# FLIGHT-CONTROLLER_VERSION-2.net
KiCad netlist of a schematic drawn in EasyEDA Pro
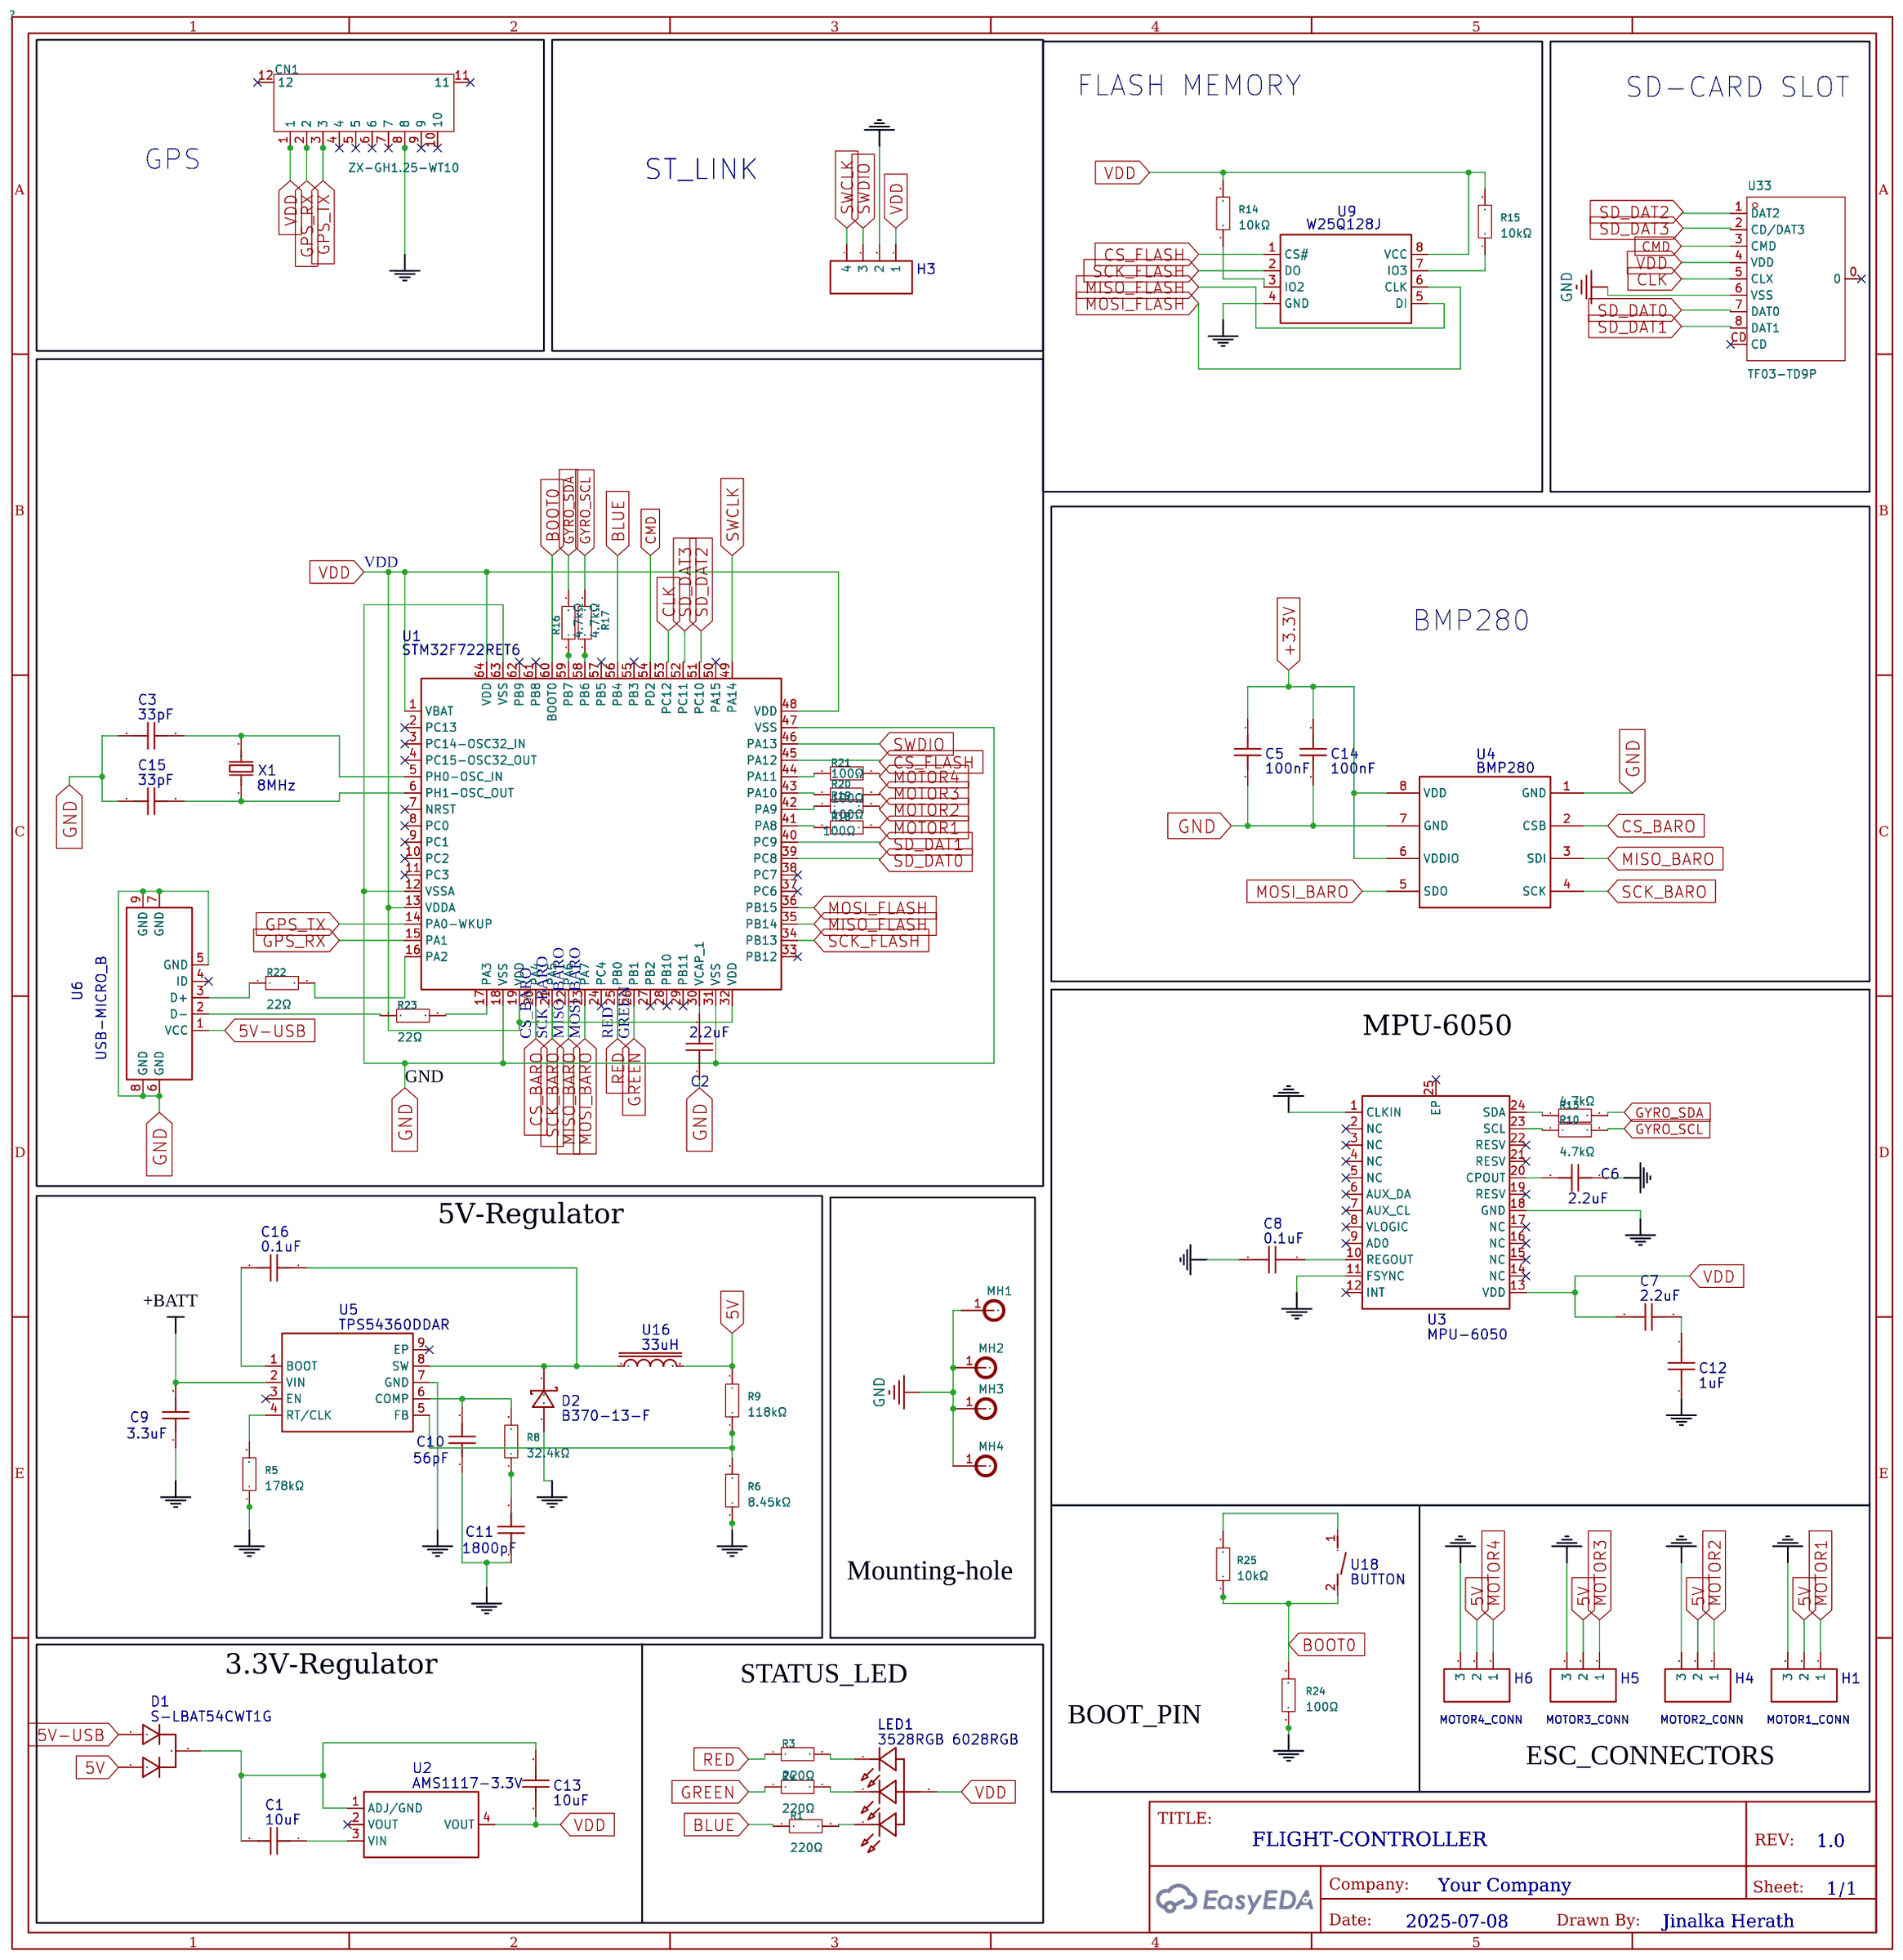
[diagram p0: schematic sheet]

(export (version "E")
  (design (tool "Eeschema 10.0.6"))
  (components
    (comp (ref "C1")
      (value "10uF")
      (footprint "easyedapro:C0603")
      (fields
        (field (name "Manufacturer Part") "C1608CH2A560J080AA")
        (field (name "Manufacturer") "TDK")
        (field (name "Contributor") "lcsc")
      )
      (libsource (lib "easyedapro") (part "10uF"))
    )
    (comp (ref "C2")
      (value "2.2uF")
      (footprint "easyedapro:CAP-SMD_L3.2-W2.5-1")
      (fields
        (field (name "Manufacturer Part") "25MU225MB23225")
        (field (name "Manufacturer") "rubycon(红宝石)")
        (field (name "Contributor") "lcsc")
      )
      (libsource (lib "easyedapro") (part "2.2uF"))
    )
    (comp (ref "C3")
      (value "33pF")
      (footprint "easyedapro:C0603")
      (fields
        (field (name "Manufacturer Part") "C1608CH2A560J080AA")
        (field (name "Manufacturer") "TDK")
        (field (name "Contributor") "lcsc")
      )
      (libsource (lib "easyedapro") (part "33pF"))
    )
    (comp (ref "C5")
      (value "100nF")
      (footprint "easyedapro:C0603")
      (fields
        (field (name "Manufacturer Part") "C1608CH2A560J080AA")
        (field (name "Manufacturer") "TDK")
        (field (name "Contributor") "lcsc")
      )
      (libsource (lib "easyedapro") (part "100nF"))
    )
    (comp (ref "C6")
      (value "2.2uF")
      (footprint "easyedapro:CAP-SMD_L3.2-W2.5-1")
      (fields
        (field (name "Manufacturer Part") "25MU225MB23225")
        (field (name "Manufacturer") "rubycon(红宝石)")
        (field (name "Contributor") "lcsc")
      )
      (libsource (lib "easyedapro") (part "2.2uF"))
    )
    (comp (ref "C7")
      (value "2.2uF")
      (footprint "easyedapro:CAP-SMD_L3.2-W2.5-1")
      (fields
        (field (name "Manufacturer Part") "25MU225MB23225")
        (field (name "Manufacturer") "rubycon(红宝石)")
        (field (name "Contributor") "lcsc")
      )
      (libsource (lib "easyedapro") (part "2.2uF"))
    )
    (comp (ref "C8")
      (value "0.1uF")
      (footprint "easyedapro:C0603")
      (fields
        (field (name "Manufacturer Part") "C1608CH2A560J080AA")
        (field (name "Manufacturer") "TDK")
        (field (name "Contributor") "lcsc")
      )
      (libsource (lib "easyedapro") (part "0.1uF"))
    )
    (comp (ref "C9")
      (value "3.3uF")
      (footprint "easyedapro:C0603")
      (fields
        (field (name "Manufacturer Part") "C1608CH2A560J080AA")
        (field (name "Manufacturer") "TDK")
        (field (name "Contributor") "lcsc")
      )
      (libsource (lib "easyedapro") (part "3.3uF"))
    )
    (comp (ref "C10")
      (value "56pF")
      (footprint "easyedapro:C0603")
      (fields
        (field (name "Manufacturer Part") "C1608CH2A560J080AA")
        (field (name "Manufacturer") "TDK")
        (field (name "Contributor") "lcsc")
      )
      (libsource (lib "easyedapro") (part "56pF"))
    )
    (comp (ref "C11")
      (value "1800pF")
      (footprint "easyedapro:C0603")
      (fields
        (field (name "Manufacturer Part") "C1608CH2A560J080AA")
        (field (name "Manufacturer") "TDK")
        (field (name "Contributor") "lcsc")
      )
      (libsource (lib "easyedapro") (part "1800pF"))
    )
    (comp (ref "C12")
      (value "1uF")
      (footprint "easyedapro:C0603")
      (fields
        (field (name "Manufacturer Part") "C1608CH2A560J080AA")
        (field (name "Manufacturer") "TDK")
        (field (name "Contributor") "lcsc")
      )
      (libsource (lib "easyedapro") (part "1uF"))
    )
    (comp (ref "C13")
      (value "10uF")
      (footprint "easyedapro:C0603")
      (fields
        (field (name "Manufacturer Part") "C1608CH2A560J080AA")
        (field (name "Manufacturer") "TDK")
        (field (name "Contributor") "lcsc")
      )
      (libsource (lib "easyedapro") (part "10uF"))
    )
    (comp (ref "C14")
      (value "100nF")
      (footprint "easyedapro:C0603")
      (fields
        (field (name "Manufacturer Part") "C1608CH2A560J080AA")
        (field (name "Manufacturer") "TDK")
        (field (name "Contributor") "lcsc")
      )
      (libsource (lib "easyedapro") (part "100nF"))
    )
    (comp (ref "C15")
      (value "33pF")
      (footprint "easyedapro:C0603")
      (fields
        (field (name "Manufacturer Part") "C1608CH2A560J080AA")
        (field (name "Manufacturer") "TDK")
        (field (name "Contributor") "lcsc")
      )
      (libsource (lib "easyedapro") (part "33pF"))
    )
    (comp (ref "C16")
      (value "0.1uF")
      (footprint "easyedapro:C0603")
      (fields
        (field (name "Manufacturer Part") "C1608CH2A560J080AA")
        (field (name "Manufacturer") "TDK")
        (field (name "Contributor") "lcsc")
      )
      (libsource (lib "easyedapro") (part "0.1uF"))
    )
    (comp (ref "CN1")
      (value "ZX-GH1.25-WT10")
      (footprint "easyedapro:CONN-SMD_ZX-GH1.25-WT10")
      (fields (field (name "Manufacturer") "Megastar(兆星)"))
      (libsource (lib "easyedapro") (part "ZX-GH1.25-WT10"))
    )
    (comp (ref "D1")
      (value "S-LBAT54CWT1G")
      (footprint "easyedapro:SC-70-3_L2.0-W1.3-P1.30-LS2.1-BR")
      (fields (field (name "Manufacturer") "LRC(乐山无线电)") (field (name "Contributor") "lcsc"))
      (libsource (lib "easyedapro") (part "S-LBAT54CWT1G"))
    )
    (comp (ref "D2")
      (value "B370-13-F")
      (footprint "easyedapro:SMC_L7.1-W6.2-LS8.1-RD")
      (fields (field (name "Manufacturer") "DIODES(美台)") (field (name "Contributor") "LCSC"))
      (libsource (lib "easyedapro") (part "B370-13-F"))
    )
    (comp (ref "H1")
      (value "MOTOR1_CONN")
      (footprint "easyedapro:HDR-F-2.54_1X3")
      (fields (field (name "Contributor") "LCEDA_Lib"))
      (libsource (lib "easyedapro") (part "MOTOR1_CONN"))
    )
    (comp (ref "H3")
      (value "ST_LINK")
      (footprint "easyedapro:HDR-F-2.54_1X4")
      (fields (field (name "Contributor") "LCEDA_Lib"))
      (libsource (lib "easyedapro") (part "ST_LINK"))
    )
    (comp (ref "H4")
      (value "MOTOR2_CONN")
      (footprint "easyedapro:HDR-F-2.54_1X3")
      (fields (field (name "Contributor") "LCEDA_Lib"))
      (libsource (lib "easyedapro") (part "MOTOR2_CONN"))
    )
    (comp (ref "H5")
      (value "MOTOR3_CONN")
      (footprint "easyedapro:HDR-F-2.54_1X3")
      (fields (field (name "Contributor") "LCEDA_Lib"))
      (libsource (lib "easyedapro") (part "MOTOR3_CONN"))
    )
    (comp (ref "H6")
      (value "MOTOR4_CONN")
      (footprint "easyedapro:HDR-F-2.54_1X3")
      (fields (field (name "Contributor") "LCEDA_Lib"))
      (libsource (lib "easyedapro") (part "MOTOR4_CONN"))
    )
    (comp (ref "LED1")
      (value "3528RGB 6028RGB")
      (footprint "easyedapro:LED-SMD_4P-L3.5-W2.8_3528RGB-6028RGB")
      (fields
        (field (name "Manufacturer Part") "3528反贴RGB 6028反贴RGB 缺口蓝色")
        (field (name "Contributor") "lcsc")
      )
      (libsource (lib "easyedapro") (part "3528RGB 6028RGB"))
    )
    (comp (ref "MH1")
      (value "~")
      (footprint "easyedapro:MH_7.5")
      (libsource (lib "easyedapro") (part "MH_7.5"))
    )
    (comp (ref "MH2")
      (value "~")
      (footprint "easyedapro:MH_7.5")
      (libsource (lib "easyedapro") (part "MH_7.5"))
    )
    (comp (ref "MH3")
      (value "~")
      (footprint "easyedapro:MH_7.5")
      (libsource (lib "easyedapro") (part "MH_7.5"))
    )
    (comp (ref "MH4")
      (value "~")
      (footprint "easyedapro:MH_7.5")
      (libsource (lib "easyedapro") (part "MH_7.5"))
    )
    (comp (ref "R1")
      (value "220Ω")
      (footprint "easyedapro:R0805")
      (fields
        (field (name "Manufacturer Part") "0805W8F2200T5E")
        (field (name "Manufacturer") "UNI-ROYAL(厚声)")
      )
      (libsource (lib "easyedapro") (part "0805W8F2200T5E"))
    )
    (comp (ref "R3")
      (value "220Ω")
      (footprint "easyedapro:R0805")
      (fields
        (field (name "Manufacturer Part") "0805W8F2200T5E")
        (field (name "Manufacturer") "UNI-ROYAL(厚声)")
      )
      (libsource (lib "easyedapro") (part "0805W8F2200T5E"))
    )
    (comp (ref "R4")
      (value "220Ω")
      (footprint "easyedapro:R0805")
      (fields
        (field (name "Manufacturer Part") "0805W8F2200T5E")
        (field (name "Manufacturer") "UNI-ROYAL(厚声)")
      )
      (libsource (lib "easyedapro") (part "0805W8F2200T5E"))
    )
    (comp (ref "R5")
      (value "178kΩ")
      (footprint "easyedapro:R0805")
      (fields
        (field (name "Manufacturer Part") "0805W8F2200T5E")
        (field (name "Manufacturer") "UNI-ROYAL(厚声)")
      )
      (libsource (lib "easyedapro") (part "0805W8F2200T5E"))
    )
    (comp (ref "R6")
      (value "8.45kΩ")
      (footprint "easyedapro:R0805")
      (fields
        (field (name "Manufacturer Part") "0805W8F2200T5E")
        (field (name "Manufacturer") "UNI-ROYAL(厚声)")
      )
      (libsource (lib "easyedapro") (part "0805W8F2200T5E"))
    )
    (comp (ref "R8")
      (value "32.4kΩ")
      (footprint "easyedapro:R0805")
      (fields
        (field (name "Manufacturer Part") "0805W8F2200T5E")
        (field (name "Manufacturer") "UNI-ROYAL(厚声)")
      )
      (libsource (lib "easyedapro") (part "0805W8F2200T5E"))
    )
    (comp (ref "R9")
      (value "118kΩ")
      (footprint "easyedapro:R0805")
      (fields
        (field (name "Manufacturer Part") "0805W8F2200T5E")
        (field (name "Manufacturer") "UNI-ROYAL(厚声)")
      )
      (libsource (lib "easyedapro") (part "0805W8F2200T5E"))
    )
    (comp (ref "R10")
      (value "4.7kΩ")
      (footprint "easyedapro:R0805")
      (fields
        (field (name "Manufacturer Part") "0805W8F2200T5E")
        (field (name "Manufacturer") "UNI-ROYAL(厚声)")
      )
      (libsource (lib "easyedapro") (part "0805W8F2200T5E"))
    )
    (comp (ref "R13")
      (value "4.7kΩ")
      (footprint "easyedapro:R0805")
      (fields
        (field (name "Manufacturer Part") "0805W8F2200T5E")
        (field (name "Manufacturer") "UNI-ROYAL(厚声)")
      )
      (libsource (lib "easyedapro") (part "0805W8F2200T5E"))
    )
    (comp (ref "R14")
      (value "10kΩ")
      (footprint "easyedapro:R0805")
      (fields
        (field (name "Manufacturer Part") "0805W8F2200T5E")
        (field (name "Manufacturer") "UNI-ROYAL(厚声)")
      )
      (libsource (lib "easyedapro") (part "0805W8F2200T5E"))
    )
    (comp (ref "R15")
      (value "10kΩ")
      (footprint "easyedapro:R0805")
      (fields
        (field (name "Manufacturer Part") "0805W8F2200T5E")
        (field (name "Manufacturer") "UNI-ROYAL(厚声)")
      )
      (libsource (lib "easyedapro") (part "0805W8F2200T5E"))
    )
    (comp (ref "R16")
      (value "4.7kΩ")
      (footprint "easyedapro:R0805")
      (fields
        (field (name "Manufacturer Part") "0805W8F2200T5E")
        (field (name "Manufacturer") "UNI-ROYAL(厚声)")
      )
      (libsource (lib "easyedapro") (part "0805W8F2200T5E"))
    )
    (comp (ref "R17")
      (value "4.7kΩ")
      (footprint "easyedapro:R0805")
      (fields
        (field (name "Manufacturer Part") "0805W8F2200T5E")
        (field (name "Manufacturer") "UNI-ROYAL(厚声)")
      )
      (libsource (lib "easyedapro") (part "0805W8F2200T5E"))
    )
    (comp (ref "R18")
      (value "100Ω")
      (footprint "easyedapro:R0805")
      (fields
        (field (name "Manufacturer Part") "0805W8F2200T5E")
        (field (name "Manufacturer") "UNI-ROYAL(厚声)")
      )
      (libsource (lib "easyedapro") (part "0805W8F2200T5E"))
    )
    (comp (ref "R19")
      (value "100Ω")
      (footprint "easyedapro:R0805")
      (fields
        (field (name "Manufacturer Part") "0805W8F2200T5E")
        (field (name "Manufacturer") "UNI-ROYAL(厚声)")
      )
      (libsource (lib "easyedapro") (part "0805W8F2200T5E"))
    )
    (comp (ref "R20")
      (value "100Ω")
      (footprint "easyedapro:R0805")
      (fields
        (field (name "Manufacturer Part") "0805W8F2200T5E")
        (field (name "Manufacturer") "UNI-ROYAL(厚声)")
      )
      (libsource (lib "easyedapro") (part "0805W8F2200T5E"))
    )
    (comp (ref "R21")
      (value "100Ω")
      (footprint "easyedapro:R0805")
      (fields
        (field (name "Manufacturer Part") "0805W8F2200T5E")
        (field (name "Manufacturer") "UNI-ROYAL(厚声)")
      )
      (libsource (lib "easyedapro") (part "0805W8F2200T5E"))
    )
    (comp (ref "R22")
      (value "22Ω")
      (footprint "easyedapro:R0805")
      (fields
        (field (name "Manufacturer Part") "0805W8F2200T5E")
        (field (name "Manufacturer") "UNI-ROYAL(厚声)")
      )
      (libsource (lib "easyedapro") (part "0805W8F2200T5E"))
    )
    (comp (ref "R23")
      (value "22Ω")
      (footprint "easyedapro:R0805")
      (fields
        (field (name "Manufacturer Part") "0805W8F2200T5E")
        (field (name "Manufacturer") "UNI-ROYAL(厚声)")
      )
      (libsource (lib "easyedapro") (part "0805W8F2200T5E"))
    )
    (comp (ref "R24")
      (value "100Ω")
      (footprint "easyedapro:R0805")
      (fields
        (field (name "Manufacturer Part") "0805W8F2200T5E")
        (field (name "Manufacturer") "UNI-ROYAL(厚声)")
      )
      (libsource (lib "easyedapro") (part "0805W8F2200T5E"))
    )
    (comp (ref "R25")
      (value "10kΩ")
      (footprint "easyedapro:R0805")
      (fields
        (field (name "Manufacturer Part") "0805W8F2200T5E")
        (field (name "Manufacturer") "UNI-ROYAL(厚声)")
      )
      (libsource (lib "easyedapro") (part "0805W8F2200T5E"))
    )
    (comp (ref "U1")
      (value "STM32F722RET6")
      (footprint "easyedapro:LQFP-64_L10.0-W10.0-P0.50-LS12.0-BL")
      (fields (field (name "Manufacturer") "ST(意法半导体)") (field (name "Contributor") "LCSC"))
      (libsource (lib "easyedapro") (part "STM32F722RET6"))
    )
    (comp (ref "U2")
      (value "AMS1117-3.3V")
      (footprint "easyedapro:SOT-223-4_L6.5-W3.5-P2.30-LS7.0-BR")
      (fields (field (name "Manufacturer") "WPMtek(维攀)") (field (name "Contributor") "LCSC"))
      (libsource (lib "easyedapro") (part "AMS1117-3.3V"))
    )
    (comp (ref "U3")
      (value "MPU-6050")
      (footprint "easyedapro:QFN-24_L4.0-W4.0-P0.50-BL-EP2.7")
      (fields (field (name "Manufacturer") "TDK InvenSense(应美盛)"))
      (libsource (lib "easyedapro") (part "MPU-6050_C24112"))
    )
    (comp (ref "U4")
      (value "BMP280")
      (footprint "easyedapro:LGA-8_L2.5-W2.0-P0.65_AMP6127")
      (fields (field (name "Manufacturer") "Bosch(博世)"))
      (libsource (lib "easyedapro") (part "BMP280"))
    )
    (comp (ref "U5")
      (value "TPS54360DDAR")
      (footprint "easyedapro:ESOP-8_L4.9-W3.9-P1.27-LS6.0-BL-EP")
      (fields
        (field (name "Manufacturer Part") "TPS54360DDAR(TOKMAS)")
        (field (name "Manufacturer") "Tokmas(托克马斯)")
        (field (name "Contributor") "lcsc")
      )
      (libsource (lib "easyedapro") (part "TPS54360DDAR(TOKMAS)"))
    )
    (comp (ref "U6")
      (value "USB-MICRO_B")
      (footprint "easyedapro:MICRO-USB-SMD_USB-MICRO_B")
      (fields (field (name "Contributor") "LCSC"))
      (libsource (lib "easyedapro") (part "USB-MICRO_B"))
    )
    (comp (ref "U9")
      (value "W25Q128J")
      (footprint "easyedapro:SOIC-8_L5.3-W5.3-P1.27-LS8.0-BL")
      (fields (field (name "Manufacturer Part") "W25Q128JVSIQ") (field (name "Manufacturer") "WINBOND(华邦)"))
      (libsource (lib "easyedapro") (part "W25Q128JVSIQTR"))
    )
    (comp (ref "U16")
      (value "33uH")
      (footprint "easyedapro:IND-SMD_L8.5-W8.0_SMS0850")
      (fields
        (field (name "Manufacturer Part") "SMS0850-330MT")
        (field (name "Manufacturer") "LanTu Micro(蓝图微电)")
        (field (name "Contributor") "lcsc")
      )
      (libsource (lib "easyedapro") (part "33uH"))
    )
    (comp (ref "U18")
      (value "BUTTON")
      (footprint "easyedapro:KEY-SMD_L6.0-W6.0-LS6.6")
      (fields (field (name "Contributor") "lcsc"))
      (libsource (lib "easyedapro") (part "BUTTON"))
    )
    (comp (ref "U33")
      (value "TF03-TD9P")
      (footprint "easyedapro:CONN-SMD_TF-001A-P")
      (fields (field (name "Manufacturer") "BXCONN(宝讯)"))
      (libsource (lib "easyedapro") (part "TF03-TD9P"))
    )
    (comp (ref "X1")
      (value "8MHz")
      (footprint "easyedapro:CRYSTAL-SMD_L3.2-W2.5_3225-8MHZ")
      (fields
        (field (name "Manufacturer Part") "X22EL89COI-111YLC-8M")
        (field (name "Manufacturer") "YXC(扬兴晶振)")
        (field (name "Contributor") "lcsc")
      )
      (libsource (lib "easyedapro") (part "8MHz"))
    )
  )
  (nets
    (net (code "1") (name "+3.3V") (class "Default")
      (node (ref "C14") (pin "1") (pinfunction "1_1") (pintype "unspecified"))
      (node (ref "C5") (pin "1") (pinfunction "1_1") (pintype "unspecified"))
      (node (ref "U4") (pin "6") (pinfunction "VDDIO_6") (pintype "unspecified"))
      (node (ref "U4") (pin "8") (pinfunction "VDD_8") (pintype "unspecified"))
    )
    (net (code "2") (name "+BATT") (class "Default")
      (node (ref "C9") (pin "2") (pinfunction "2_2") (pintype "unspecified"))
      (node (ref "U5") (pin "2") (pinfunction "VIN_2") (pintype "unspecified"))
    )
    (net (code "3") (name "5V") (class "Default")
      (node (ref "D1") (pin "2") (pinfunction "2_2") (pintype "unspecified"))
      (node (ref "H1") (pin "2") (pinfunction "2_2") (pintype "input"))
      (node (ref "H4") (pin "2") (pinfunction "2_2") (pintype "input"))
      (node (ref "H5") (pin "2") (pinfunction "2_2") (pintype "input"))
      (node (ref "H6") (pin "2") (pinfunction "2_2") (pintype "input"))
      (node (ref "R9") (pin "2") (pinfunction "2_2") (pintype "input"))
      (node (ref "U16") (pin "2") (pinfunction "2_2") (pintype "unspecified"))
    )
    (net (code "4") (name "5V-USB") (class "Default")
      (node (ref "D1") (pin "1") (pinfunction "1_1") (pintype "unspecified"))
      (node (ref "U6") (pin "1") (pinfunction "VCC_1") (pintype "unspecified"))
    )
    (net (code "5") (name "BLUE") (class "Default")
      (node (ref "R1") (pin "1") (pinfunction "1_1") (pintype "input"))
      (node (ref "U1") (pin "56") (pinfunction "PB4_56") (pintype "unspecified"))
    )
    (net (code "6") (name "BOOT0") (class "Default")
      (node (ref "R24") (pin "2") (pinfunction "2_2") (pintype "input"))
      (node (ref "R25") (pin "1") (pinfunction "1_1") (pintype "input"))
      (node (ref "U1") (pin "60") (pinfunction "BOOT0_60") (pintype "unspecified"))
      (node (ref "U18") (pin "2") (pinfunction "B_2") (pintype "unspecified"))
    )
    (net (code "7") (name "CLK") (class "Default")
      (node (ref "U1") (pin "53") (pinfunction "PC12_53") (pintype "unspecified"))
      (node (ref "U33") (pin "5") (pinfunction "CLX_5") (pintype "unspecified"))
    )
    (net (code "8") (name "CMD") (class "Default")
      (node (ref "U1") (pin "54") (pinfunction "PD2_54") (pintype "unspecified"))
      (node (ref "U33") (pin "3") (pinfunction "CMD_3") (pintype "unspecified"))
    )
    (net (code "9") (name "CS_BARO") (class "Default")
      (node (ref "U1") (pin "20") (pinfunction "PA4_20") (pintype "unspecified"))
      (node (ref "U4") (pin "2") (pinfunction "CSB_2") (pintype "unspecified"))
    )
    (net (code "10") (name "CS_FLASH") (class "Default")
      (node (ref "U1") (pin "45") (pinfunction "PA12_45") (pintype "unspecified"))
      (node (ref "U9") (pin "1") (pinfunction "CS#_1") (pintype "unspecified"))
    )
    (net (code "11") (name "GND") (class "Default")
      (node (ref "C10") (pin "1") (pinfunction "1_1") (pintype "unspecified"))
      (node (ref "C11") (pin "1") (pinfunction "1_1") (pintype "unspecified"))
      (node (ref "C12") (pin "2") (pinfunction "2_2") (pintype "unspecified"))
      (node (ref "C14") (pin "2") (pinfunction "2_2") (pintype "unspecified"))
      (node (ref "C15") (pin "1") (pinfunction "1_1") (pintype "unspecified"))
      (node (ref "C2") (pin "1") (pinfunction "1_1") (pintype "unspecified"))
      (node (ref "C3") (pin "1") (pinfunction "1_1") (pintype "unspecified"))
      (node (ref "C5") (pin "2") (pinfunction "2_2") (pintype "unspecified"))
      (node (ref "C6") (pin "1") (pinfunction "1_1") (pintype "unspecified"))
      (node (ref "C8") (pin "2") (pinfunction "2_2") (pintype "unspecified"))
      (node (ref "C9") (pin "1") (pinfunction "1_1") (pintype "unspecified"))
      (node (ref "CN1") (pin "8") (pinfunction "8_8") (pintype "unspecified"))
      (node (ref "D2") (pin "2") (pinfunction "A_2") (pintype "unspecified"))
      (node (ref "H1") (pin "3") (pinfunction "3_3") (pintype "input"))
      (node (ref "H3") (pin "2") (pinfunction "2_2") (pintype "unspecified"))
      (node (ref "H4") (pin "3") (pinfunction "3_3") (pintype "input"))
      (node (ref "H5") (pin "3") (pinfunction "3_3") (pintype "input"))
      (node (ref "H6") (pin "3") (pinfunction "3_3") (pintype "input"))
      (node (ref "MH1") (pin "1") (pinfunction "1_1") (pintype "input"))
      (node (ref "MH2") (pin "1") (pinfunction "1_1") (pintype "input"))
      (node (ref "MH3") (pin "1") (pinfunction "1_1") (pintype "input"))
      (node (ref "MH4") (pin "1") (pinfunction "1_1") (pintype "input"))
      (node (ref "R24") (pin "1") (pinfunction "1_1") (pintype "input"))
      (node (ref "R5") (pin "1") (pinfunction "1_1") (pintype "input"))
      (node (ref "R6") (pin "1") (pinfunction "1_1") (pintype "input"))
      (node (ref "U1") (pin "12") (pinfunction "VSSA_12") (pintype "unspecified"))
      (node (ref "U1") (pin "18") (pinfunction "VSS_18") (pintype "unspecified"))
      (node (ref "U1") (pin "31") (pinfunction "VSS_31") (pintype "unspecified"))
      (node (ref "U1") (pin "47") (pinfunction "VSS_47") (pintype "unspecified"))
      (node (ref "U1") (pin "63") (pinfunction "VSS_63") (pintype "unspecified"))
      (node (ref "U3") (pin "1") (pinfunction "CLKIN_1") (pintype "unspecified"))
      (node (ref "U3") (pin "11") (pinfunction "FSYNC_11") (pintype "unspecified"))
      (node (ref "U3") (pin "18") (pinfunction "GND_18") (pintype "unspecified"))
      (node (ref "U33") (pin "6") (pinfunction "VSS_6") (pintype "unspecified"))
      (node (ref "U4") (pin "1") (pinfunction "GND_1") (pintype "unspecified"))
      (node (ref "U4") (pin "7") (pinfunction "GND_7") (pintype "unspecified"))
      (node (ref "U5") (pin "7") (pinfunction "GND_7") (pintype "unspecified"))
      (node (ref "U6") (pin "5") (pinfunction "GND_5") (pintype "unspecified"))
      (node (ref "U6") (pin "6") (pinfunction "GND_6") (pintype "unspecified"))
      (node (ref "U6") (pin "7") (pinfunction "GND_7") (pintype "unspecified"))
      (node (ref "U6") (pin "8") (pinfunction "GND_8") (pintype "unspecified"))
      (node (ref "U6") (pin "9") (pinfunction "GND_9") (pintype "unspecified"))
      (node (ref "U9") (pin "4") (pinfunction "GND_4") (pintype "unspecified"))
    )
    (net (code "12") (name "GPS_RX") (class "Default")
      (node (ref "CN1") (pin "2") (pinfunction "2_2") (pintype "unspecified"))
      (node (ref "U1") (pin "15") (pinfunction "PA1_15") (pintype "unspecified"))
    )
    (net (code "13") (name "GPS_TX") (class "Default")
      (node (ref "CN1") (pin "3") (pinfunction "3_3") (pintype "unspecified"))
      (node (ref "U1") (pin "14") (pinfunction "PA0-WKUP_14") (pintype "unspecified"))
    )
    (net (code "14") (name "GREEN") (class "Default")
      (node (ref "R4") (pin "1") (pinfunction "1_1") (pintype "input"))
      (node (ref "U1") (pin "26") (pinfunction "PB1_26") (pintype "unspecified"))
    )
    (net (code "15") (name "GYRO_SCL") (class "Default")
      (node (ref "R10") (pin "2") (pinfunction "2_2") (pintype "input"))
      (node (ref "R17") (pin "2") (pinfunction "2_2") (pintype "input"))
    )
    (net (code "16") (name "GYRO_SDA") (class "Default")
      (node (ref "R13") (pin "2") (pinfunction "2_2") (pintype "input"))
      (node (ref "R16") (pin "2") (pinfunction "2_2") (pintype "input"))
    )
    (net (code "17") (name "MISO_BARO") (class "Default")
      (node (ref "U1") (pin "22") (pinfunction "PA6_22") (pintype "unspecified"))
      (node (ref "U4") (pin "3") (pinfunction "SDI_3") (pintype "unspecified"))
    )
    (net (code "18") (name "MISO_FLASH") (class "Default")
      (node (ref "U1") (pin "35") (pinfunction "PB14_35") (pintype "unspecified"))
      (node (ref "U9") (pin "5") (pinfunction "DI_5") (pintype "unspecified"))
    )
    (net (code "19") (name "MOSI_BARO") (class "Default")
      (node (ref "U1") (pin "23") (pinfunction "PA7_23") (pintype "unspecified"))
      (node (ref "U4") (pin "5") (pinfunction "SDO_5") (pintype "unspecified"))
    )
    (net (code "20") (name "MOSI_FLASH") (class "Default")
      (node (ref "U1") (pin "36") (pinfunction "PB15_36") (pintype "unspecified"))
      (node (ref "U9") (pin "6") (pinfunction "CLK_6") (pintype "unspecified"))
    )
    (net (code "21") (name "MOTOR1") (class "Default")
      (node (ref "H1") (pin "1") (pinfunction "1_1") (pintype "input"))
      (node (ref "R18") (pin "2") (pinfunction "2_2") (pintype "input"))
    )
    (net (code "22") (name "MOTOR2") (class "Default")
      (node (ref "H4") (pin "1") (pinfunction "1_1") (pintype "input"))
      (node (ref "R19") (pin "2") (pinfunction "2_2") (pintype "input"))
    )
    (net (code "23") (name "MOTOR3") (class "Default")
      (node (ref "H5") (pin "1") (pinfunction "1_1") (pintype "input"))
      (node (ref "R20") (pin "2") (pinfunction "2_2") (pintype "input"))
    )
    (net (code "24") (name "MOTOR4") (class "Default")
      (node (ref "H6") (pin "1") (pinfunction "1_1") (pintype "input"))
      (node (ref "R21") (pin "2") (pinfunction "2_2") (pintype "input"))
    )
    (net (code "25") (name "Net-(C11-Pad2)") (class "Default")
      (node (ref "C11") (pin "2") (pinfunction "2_2") (pintype "unspecified"))
      (node (ref "R8") (pin "1") (pinfunction "1_1") (pintype "input"))
    )
    (net (code "26") (name "Net-(C12-Pad1)") (class "Default")
      (node (ref "C12") (pin "1") (pinfunction "1_1") (pintype "unspecified"))
      (node (ref "C7") (pin "1") (pinfunction "1_1") (pintype "unspecified"))
    )
    (net (code "27") (name "Net-(D2-C)") (class "Default")
      (node (ref "C16") (pin "1") (pinfunction "1_1") (pintype "unspecified"))
      (node (ref "D2") (pin "1") (pinfunction "C_1") (pintype "unspecified"))
      (node (ref "U16") (pin "1") (pinfunction "1_1") (pintype "unspecified"))
      (node (ref "U5") (pin "8") (pinfunction "SW_8") (pintype "unspecified"))
    )
    (net (code "28") (name "Net-(LED1-B)") (class "Default")
      (node (ref "LED1") (pin "1") (pinfunction "B_1") (pintype "unspecified"))
      (node (ref "R4") (pin "2") (pinfunction "2_2") (pintype "input"))
    )
    (net (code "29") (name "Net-(LED1-G)") (class "Default")
      (node (ref "LED1") (pin "4") (pinfunction "G_4") (pintype "unspecified"))
      (node (ref "R1") (pin "2") (pinfunction "2_2") (pintype "input"))
    )
    (net (code "30") (name "Net-(LED1-R)") (class "Default")
      (node (ref "LED1") (pin "2") (pinfunction "R_2") (pintype "unspecified"))
      (node (ref "R3") (pin "2") (pinfunction "2_2") (pintype "input"))
    )
    (net (code "31") (name "Net-(U1-PA2)") (class "Default")
      (node (ref "R22") (pin "2") (pinfunction "2_2") (pintype "input"))
      (node (ref "U1") (pin "16") (pinfunction "PA2_16") (pintype "unspecified"))
    )
    (net (code "32") (name "Net-(U1-PA3)") (class "Default")
      (node (ref "R23") (pin "2") (pinfunction "2_2") (pintype "input"))
      (node (ref "U1") (pin "17") (pinfunction "PA3_17") (pintype "unspecified"))
    )
    (net (code "33") (name "Net-(U1-PA8)") (class "Default")
      (node (ref "R18") (pin "1") (pinfunction "1_1") (pintype "input"))
      (node (ref "U1") (pin "41") (pinfunction "PA8_41") (pintype "unspecified"))
    )
    (net (code "34") (name "Net-(U1-PA9)") (class "Default")
      (node (ref "R19") (pin "1") (pinfunction "1_1") (pintype "input"))
      (node (ref "U1") (pin "42") (pinfunction "PA9_42") (pintype "unspecified"))
    )
    (net (code "35") (name "Net-(U1-PA10)") (class "Default")
      (node (ref "R20") (pin "1") (pinfunction "1_1") (pintype "input"))
      (node (ref "U1") (pin "43") (pinfunction "PA10_43") (pintype "unspecified"))
    )
    (net (code "36") (name "Net-(U1-PA11)") (class "Default")
      (node (ref "R21") (pin "1") (pinfunction "1_1") (pintype "input"))
      (node (ref "U1") (pin "44") (pinfunction "PA11_44") (pintype "unspecified"))
    )
    (net (code "37") (name "Net-(U1-PB6)") (class "Default")
      (node (ref "R17") (pin "1") (pinfunction "1_1") (pintype "input"))
      (node (ref "U1") (pin "58") (pinfunction "PB6_58") (pintype "unspecified"))
    )
    (net (code "38") (name "Net-(U1-PB7)") (class "Default")
      (node (ref "R16") (pin "1") (pinfunction "1_1") (pintype "input"))
      (node (ref "U1") (pin "59") (pinfunction "PB7_59") (pintype "unspecified"))
    )
    (net (code "39") (name "Net-(U1-PH0-OSC_IN)") (class "Default")
      (node (ref "C3") (pin "2") (pinfunction "2_2") (pintype "unspecified"))
      (node (ref "U1") (pin "5") (pinfunction "PH0-OSC_IN_5") (pintype "unspecified"))
      (node (ref "X1") (pin "2") (pinfunction "2_2") (pintype "unspecified"))
    )
    (net (code "40") (name "Net-(U1-PH1-OSC_OUT)") (class "Default")
      (node (ref "C15") (pin "2") (pinfunction "2_2") (pintype "unspecified"))
      (node (ref "U1") (pin "6") (pinfunction "PH1-OSC_OUT_6") (pintype "unspecified"))
      (node (ref "X1") (pin "1") (pinfunction "1_1") (pintype "unspecified"))
    )
    (net (code "41") (name "Net-(U1-VCAP_1)") (class "Default")
      (node (ref "C2") (pin "2") (pinfunction "2_2") (pintype "unspecified"))
      (node (ref "U1") (pin "30") (pinfunction "VCAP_1_30") (pintype "unspecified"))
    )
    (net (code "42") (name "Net-(U2-ADJ{slash}GND)") (class "Default")
      (node (ref "C1") (pin "2") (pinfunction "2_2") (pintype "unspecified"))
      (node (ref "C13") (pin "1") (pinfunction "1_1") (pintype "unspecified"))
      (node (ref "D1") (pin "3") (pinfunction "3_3") (pintype "unspecified"))
      (node (ref "U2") (pin "1") (pinfunction "ADJ/GND_1") (pintype "unspecified"))
    )
    (net (code "43") (name "Net-(U2-VIN)") (class "Default")
      (node (ref "C1") (pin "1") (pinfunction "1_1") (pintype "unspecified"))
      (node (ref "U2") (pin "3") (pinfunction "VIN_3") (pintype "unspecified"))
    )
    (net (code "44") (name "Net-(U3-CPOUT)") (class "Default")
      (node (ref "C6") (pin "2") (pinfunction "2_2") (pintype "unspecified"))
      (node (ref "U3") (pin "20") (pinfunction "CPOUT_20") (pintype "unspecified"))
    )
    (net (code "45") (name "Net-(U3-REGOUT)") (class "Default")
      (node (ref "C8") (pin "1") (pinfunction "1_1") (pintype "unspecified"))
      (node (ref "U3") (pin "10") (pinfunction "REGOUT_10") (pintype "unspecified"))
    )
    (net (code "46") (name "Net-(U3-SCL)") (class "Default")
      (node (ref "R10") (pin "1") (pinfunction "1_1") (pintype "input"))
      (node (ref "U3") (pin "23") (pinfunction "SCL_23") (pintype "unspecified"))
    )
    (net (code "47") (name "Net-(U3-SDA)") (class "Default")
      (node (ref "R13") (pin "1") (pinfunction "1_1") (pintype "input"))
      (node (ref "U3") (pin "24") (pinfunction "SDA_24") (pintype "unspecified"))
    )
    (net (code "48") (name "Net-(U5-BOOT)") (class "Default")
      (node (ref "C16") (pin "2") (pinfunction "2_2") (pintype "unspecified"))
      (node (ref "U5") (pin "1") (pinfunction "BOOT_1") (pintype "unspecified"))
    )
    (net (code "49") (name "Net-(U5-COMP)") (class "Default")
      (node (ref "C10") (pin "2") (pinfunction "2_2") (pintype "unspecified"))
      (node (ref "R8") (pin "2") (pinfunction "2_2") (pintype "input"))
      (node (ref "U5") (pin "6") (pinfunction "COMP_6") (pintype "unspecified"))
    )
    (net (code "50") (name "Net-(U5-FB)") (class "Default")
      (node (ref "R6") (pin "2") (pinfunction "2_2") (pintype "input"))
      (node (ref "R9") (pin "1") (pinfunction "1_1") (pintype "input"))
      (node (ref "U5") (pin "5") (pinfunction "FB_5") (pintype "unspecified"))
    )
    (net (code "51") (name "Net-(U5-RT{slash}CLK)") (class "Default")
      (node (ref "R5") (pin "2") (pinfunction "2_2") (pintype "input"))
      (node (ref "U5") (pin "4") (pinfunction "RT/CLK_4") (pintype "unspecified"))
    )
    (net (code "52") (name "Net-(U6-D+)") (class "Default")
      (node (ref "R22") (pin "1") (pinfunction "1_1") (pintype "input"))
      (node (ref "U6") (pin "3") (pinfunction "D+_3") (pintype "unspecified"))
    )
    (net (code "53") (name "Net-(U6-D-)") (class "Default")
      (node (ref "R23") (pin "1") (pinfunction "1_1") (pintype "input"))
      (node (ref "U6") (pin "2") (pinfunction "D-_2") (pintype "unspecified"))
    )
    (net (code "54") (name "Net-(U9-IO2)") (class "Default")
      (node (ref "R14") (pin "1") (pinfunction "1_1") (pintype "input"))
      (node (ref "U9") (pin "3") (pinfunction "IO2_3") (pintype "unspecified"))
    )
    (net (code "55") (name "Net-(U9-IO3)") (class "Default")
      (node (ref "R15") (pin "1") (pinfunction "1_1") (pintype "input"))
      (node (ref "U9") (pin "7") (pinfunction "IO3_7") (pintype "unspecified"))
    )
    (net (code "56") (name "Net-(U18-A)") (class "Default")
      (node (ref "R25") (pin "2") (pinfunction "2_2") (pintype "input"))
      (node (ref "U18") (pin "1") (pinfunction "A_1") (pintype "unspecified"))
    )
    (net (code "57") (name "RED") (class "Default")
      (node (ref "R3") (pin "1") (pinfunction "1_1") (pintype "input"))
      (node (ref "U1") (pin "25") (pinfunction "PB0_25") (pintype "unspecified"))
    )
    (net (code "58") (name "SCK_BARO") (class "Default")
      (node (ref "U1") (pin "21") (pinfunction "PA5_21") (pintype "unspecified"))
      (node (ref "U4") (pin "4") (pinfunction "SCK_4") (pintype "unspecified"))
    )
    (net (code "59") (name "SCK_FLASH") (class "Default")
      (node (ref "U1") (pin "34") (pinfunction "PB13_34") (pintype "unspecified"))
      (node (ref "U9") (pin "2") (pinfunction "DO_2") (pintype "unspecified"))
    )
    (net (code "60") (name "SD_DAT0") (class "Default")
      (node (ref "U1") (pin "39") (pinfunction "PC8_39") (pintype "unspecified"))
      (node (ref "U33") (pin "7") (pinfunction "DAT0_7") (pintype "unspecified"))
    )
    (net (code "61") (name "SD_DAT1") (class "Default")
      (node (ref "U1") (pin "40") (pinfunction "PC9_40") (pintype "unspecified"))
      (node (ref "U33") (pin "8") (pinfunction "DAT1_8") (pintype "unspecified"))
    )
    (net (code "62") (name "SD_DAT2") (class "Default")
      (node (ref "U1") (pin "51") (pinfunction "PC10_51") (pintype "unspecified"))
      (node (ref "U33") (pin "1") (pinfunction "DAT2_1") (pintype "unspecified"))
    )
    (net (code "63") (name "SD_DAT3") (class "Default")
      (node (ref "U1") (pin "52") (pinfunction "PC11_52") (pintype "unspecified"))
      (node (ref "U33") (pin "2") (pinfunction "CD/DAT3_2") (pintype "unspecified"))
    )
    (net (code "64") (name "SWCLK") (class "Default")
      (node (ref "H3") (pin "4") (pinfunction "4_4") (pintype "unspecified"))
      (node (ref "U1") (pin "49") (pinfunction "PA14_49") (pintype "unspecified"))
    )
    (net (code "65") (name "SWDIO") (class "Default")
      (node (ref "H3") (pin "3") (pinfunction "3_3") (pintype "unspecified"))
      (node (ref "U1") (pin "46") (pinfunction "PA13_46") (pintype "unspecified"))
    )
    (net (code "66") (name "VDD") (class "Default")
      (node (ref "C13") (pin "2") (pinfunction "2_2") (pintype "unspecified"))
      (node (ref "C7") (pin "2") (pinfunction "2_2") (pintype "unspecified"))
      (node (ref "CN1") (pin "1") (pinfunction "1_1") (pintype "unspecified"))
      (node (ref "H3") (pin "1") (pinfunction "1_1") (pintype "unspecified"))
      (node (ref "LED1") (pin "3") (pinfunction "A_3") (pintype "unspecified"))
      (node (ref "R14") (pin "2") (pinfunction "2_2") (pintype "input"))
      (node (ref "R15") (pin "2") (pinfunction "2_2") (pintype "input"))
      (node (ref "U1") (pin "1") (pinfunction "VBAT_1") (pintype "unspecified"))
      (node (ref "U1") (pin "13") (pinfunction "VDDA_13") (pintype "unspecified"))
      (node (ref "U1") (pin "19") (pinfunction "VDD_19") (pintype "unspecified"))
      (node (ref "U1") (pin "32") (pinfunction "VDD_32") (pintype "unspecified"))
      (node (ref "U1") (pin "48") (pinfunction "VDD_48") (pintype "unspecified"))
      (node (ref "U1") (pin "64") (pinfunction "VDD_64") (pintype "unspecified"))
      (node (ref "U2") (pin "4") (pinfunction "VOUT_4") (pintype "unspecified"))
      (node (ref "U3") (pin "13") (pinfunction "VDD_13") (pintype "unspecified"))
      (node (ref "U33") (pin "4") (pinfunction "VDD_4") (pintype "unspecified"))
      (node (ref "U9") (pin "8") (pinfunction "VCC_8") (pintype "unspecified"))
    )
    (net (code "67") (name "unconnected-(CN1-Pad4)") (class "Default")
      (node (ref "CN1") (pin "4") (pinfunction "4_4") (pintype "unspecified+no_connect"))
    )
    (net (code "68") (name "unconnected-(CN1-Pad5)") (class "Default")
      (node (ref "CN1") (pin "5") (pinfunction "5_5") (pintype "unspecified+no_connect"))
    )
    (net (code "69") (name "unconnected-(CN1-Pad6)") (class "Default")
      (node (ref "CN1") (pin "6") (pinfunction "6_6") (pintype "unspecified+no_connect"))
    )
    (net (code "70") (name "unconnected-(CN1-Pad7)") (class "Default")
      (node (ref "CN1") (pin "7") (pinfunction "7_7") (pintype "unspecified+no_connect"))
    )
    (net (code "71") (name "unconnected-(CN1-Pad9)") (class "Default")
      (node (ref "CN1") (pin "9") (pinfunction "9_9") (pintype "unspecified+no_connect"))
    )
    (net (code "72") (name "unconnected-(CN1-Pad10)") (class "Default")
      (node (ref "CN1") (pin "10") (pinfunction "10_10") (pintype "unspecified+no_connect"))
    )
    (net (code "73") (name "unconnected-(CN1-Pad11)") (class "Default")
      (node (ref "CN1") (pin "11") (pinfunction "11_11") (pintype "unspecified+no_connect"))
    )
    (net (code "74") (name "unconnected-(CN1-Pad12)") (class "Default")
      (node (ref "CN1") (pin "12") (pinfunction "12_12") (pintype "unspecified+no_connect"))
    )
    (net (code "75") (name "unconnected-(U1-NRST-Pad7)") (class "Default")
      (node (ref "U1") (pin "7") (pinfunction "NRST_7") (pintype "unspecified+no_connect"))
    )
    (net (code "76") (name "unconnected-(U1-PA15-Pad50)") (class "Default")
      (node (ref "U1") (pin "50") (pinfunction "PA15_50") (pintype "unspecified+no_connect"))
    )
    (net (code "77") (name "unconnected-(U1-PB2-Pad27)") (class "Default")
      (node (ref "U1") (pin "27") (pinfunction "PB2_27") (pintype "unspecified+no_connect"))
    )
    (net (code "78") (name "unconnected-(U1-PB3-Pad55)") (class "Default")
      (node (ref "U1") (pin "55") (pinfunction "PB3_55") (pintype "unspecified+no_connect"))
    )
    (net (code "79") (name "unconnected-(U1-PB5-Pad57)") (class "Default")
      (node (ref "U1") (pin "57") (pinfunction "PB5_57") (pintype "unspecified+no_connect"))
    )
    (net (code "80") (name "unconnected-(U1-PB8-Pad61)") (class "Default")
      (node (ref "U1") (pin "61") (pinfunction "PB8_61") (pintype "unspecified+no_connect"))
    )
    (net (code "81") (name "unconnected-(U1-PB9-Pad62)") (class "Default")
      (node (ref "U1") (pin "62") (pinfunction "PB9_62") (pintype "unspecified+no_connect"))
    )
    (net (code "82") (name "unconnected-(U1-PB10-Pad28)") (class "Default")
      (node (ref "U1") (pin "28") (pinfunction "PB10_28") (pintype "unspecified+no_connect"))
    )
    (net (code "83") (name "unconnected-(U1-PB11-Pad29)") (class "Default")
      (node (ref "U1") (pin "29") (pinfunction "PB11_29") (pintype "unspecified+no_connect"))
    )
    (net (code "84") (name "unconnected-(U1-PB12-Pad33)") (class "Default")
      (node (ref "U1") (pin "33") (pinfunction "PB12_33") (pintype "unspecified+no_connect"))
    )
    (net (code "85") (name "unconnected-(U1-PC0-Pad8)") (class "Default")
      (node (ref "U1") (pin "8") (pinfunction "PC0_8") (pintype "unspecified+no_connect"))
    )
    (net (code "86") (name "unconnected-(U1-PC1-Pad9)") (class "Default")
      (node (ref "U1") (pin "9") (pinfunction "PC1_9") (pintype "unspecified+no_connect"))
    )
    (net (code "87") (name "unconnected-(U1-PC2-Pad10)") (class "Default")
      (node (ref "U1") (pin "10") (pinfunction "PC2_10") (pintype "unspecified+no_connect"))
    )
    (net (code "88") (name "unconnected-(U1-PC3-Pad11)") (class "Default")
      (node (ref "U1") (pin "11") (pinfunction "PC3_11") (pintype "unspecified+no_connect"))
    )
    (net (code "89") (name "unconnected-(U1-PC4-Pad24)") (class "Default")
      (node (ref "U1") (pin "24") (pinfunction "PC4_24") (pintype "unspecified+no_connect"))
    )
    (net (code "90") (name "unconnected-(U1-PC6-Pad37)") (class "Default")
      (node (ref "U1") (pin "37") (pinfunction "PC6_37") (pintype "unspecified+no_connect"))
    )
    (net (code "91") (name "unconnected-(U1-PC7-Pad38)") (class "Default")
      (node (ref "U1") (pin "38") (pinfunction "PC7_38") (pintype "unspecified+no_connect"))
    )
    (net (code "92") (name "unconnected-(U1-PC13-Pad2)") (class "Default")
      (node (ref "U1") (pin "2") (pinfunction "PC13_2") (pintype "unspecified+no_connect"))
    )
    (net (code "93") (name "unconnected-(U1-PC14-OSC32_IN-Pad3)") (class "Default")
      (node (ref "U1") (pin "3") (pinfunction "PC14-OSC32_IN_3") (pintype "unspecified+no_connect"))
    )
    (net (code "94") (name "unconnected-(U1-PC15-OSC32_OUT-Pad4)") (class "Default")
      (node (ref "U1") (pin "4") (pinfunction "PC15-OSC32_OUT_4") (pintype "unspecified+no_connect"))
    )
    (net (code "95") (name "unconnected-(U2-VOUT-Pad2)") (class "Default")
      (node (ref "U2") (pin "2") (pinfunction "VOUT_2") (pintype "unspecified+no_connect"))
    )
    (net (code "96") (name "unconnected-(U3-AD0-Pad9)") (class "Default")
      (node (ref "U3") (pin "9") (pinfunction "AD0_9") (pintype "unspecified+no_connect"))
    )
    (net (code "97") (name "unconnected-(U3-AUX_CL-Pad7)") (class "Default")
      (node (ref "U3") (pin "7") (pinfunction "AUX_CL_7") (pintype "unspecified+no_connect"))
    )
    (net (code "98") (name "unconnected-(U3-AUX_DA-Pad6)") (class "Default")
      (node (ref "U3") (pin "6") (pinfunction "AUX_DA_6") (pintype "unspecified+no_connect"))
    )
    (net (code "99") (name "unconnected-(U3-EP-Pad25)") (class "Default")
      (node (ref "U3") (pin "25") (pinfunction "EP_25") (pintype "unspecified+no_connect"))
    )
    (net (code "100") (name "unconnected-(U3-INT-Pad12)") (class "Default")
      (node (ref "U3") (pin "12") (pinfunction "INT_12") (pintype "unspecified+no_connect"))
    )
    (net (code "101") (name "unconnected-(U3-NC-Pad2)") (class "Default")
      (node (ref "U3") (pin "2") (pinfunction "NC_2") (pintype "unspecified+no_connect"))
    )
    (net (code "102") (name "unconnected-(U3-NC-Pad3)") (class "Default")
      (node (ref "U3") (pin "3") (pinfunction "NC_3") (pintype "unspecified+no_connect"))
    )
    (net (code "103") (name "unconnected-(U3-NC-Pad4)") (class "Default")
      (node (ref "U3") (pin "4") (pinfunction "NC_4") (pintype "unspecified+no_connect"))
    )
    (net (code "104") (name "unconnected-(U3-NC-Pad5)") (class "Default")
      (node (ref "U3") (pin "5") (pinfunction "NC_5") (pintype "unspecified+no_connect"))
    )
    (net (code "105") (name "unconnected-(U3-NC-Pad14)") (class "Default")
      (node (ref "U3") (pin "14") (pinfunction "NC_14") (pintype "unspecified+no_connect"))
    )
    (net (code "106") (name "unconnected-(U3-NC-Pad15)") (class "Default")
      (node (ref "U3") (pin "15") (pinfunction "NC_15") (pintype "unspecified+no_connect"))
    )
    (net (code "107") (name "unconnected-(U3-NC-Pad16)") (class "Default")
      (node (ref "U3") (pin "16") (pinfunction "NC_16") (pintype "unspecified+no_connect"))
    )
    (net (code "108") (name "unconnected-(U3-NC-Pad17)") (class "Default")
      (node (ref "U3") (pin "17") (pinfunction "NC_17") (pintype "unspecified+no_connect"))
    )
    (net (code "109") (name "unconnected-(U3-RESV-Pad19)") (class "Default")
      (node (ref "U3") (pin "19") (pinfunction "RESV_19") (pintype "unspecified+no_connect"))
    )
    (net (code "110") (name "unconnected-(U3-RESV-Pad21)") (class "Default")
      (node (ref "U3") (pin "21") (pinfunction "RESV_21") (pintype "unspecified+no_connect"))
    )
    (net (code "111") (name "unconnected-(U3-RESV-Pad22)") (class "Default")
      (node (ref "U3") (pin "22") (pinfunction "RESV_22") (pintype "unspecified+no_connect"))
    )
    (net (code "112") (name "unconnected-(U3-VLOGIC-Pad8)") (class "Default")
      (node (ref "U3") (pin "8") (pinfunction "VLOGIC_8") (pintype "unspecified+no_connect"))
    )
    (net (code "113") (name "unconnected-(U5-EN-Pad3)") (class "Default")
      (node (ref "U5") (pin "3") (pinfunction "EN_3") (pintype "unspecified+no_connect"))
    )
    (net (code "114") (name "unconnected-(U5-EP-Pad9)") (class "Default")
      (node (ref "U5") (pin "9") (pinfunction "EP_9") (pintype "unspecified+no_connect"))
    )
    (net (code "115") (name "unconnected-(U6-ID-Pad4)") (class "Default")
      (node (ref "U6") (pin "4") (pinfunction "ID_4") (pintype "unspecified+no_connect"))
    )
    (net (code "116") (name "unconnected-(U33-Pad0)") (class "Default")
      (node (ref "U33") (pin "0") (pinfunction "0_0") (pintype "unspecified+no_connect"))
    )
    (net (code "117") (name "unconnected-(U33-PadCD)") (class "Default")
      (node (ref "U33") (pin "CD") (pinfunction "CD_CD") (pintype "unspecified+no_connect"))
    )
  )
)
